# assignment_NOVA_TEAM_light_control_syste.net
KiCad netlist of a schematic drawn in EasyEDA
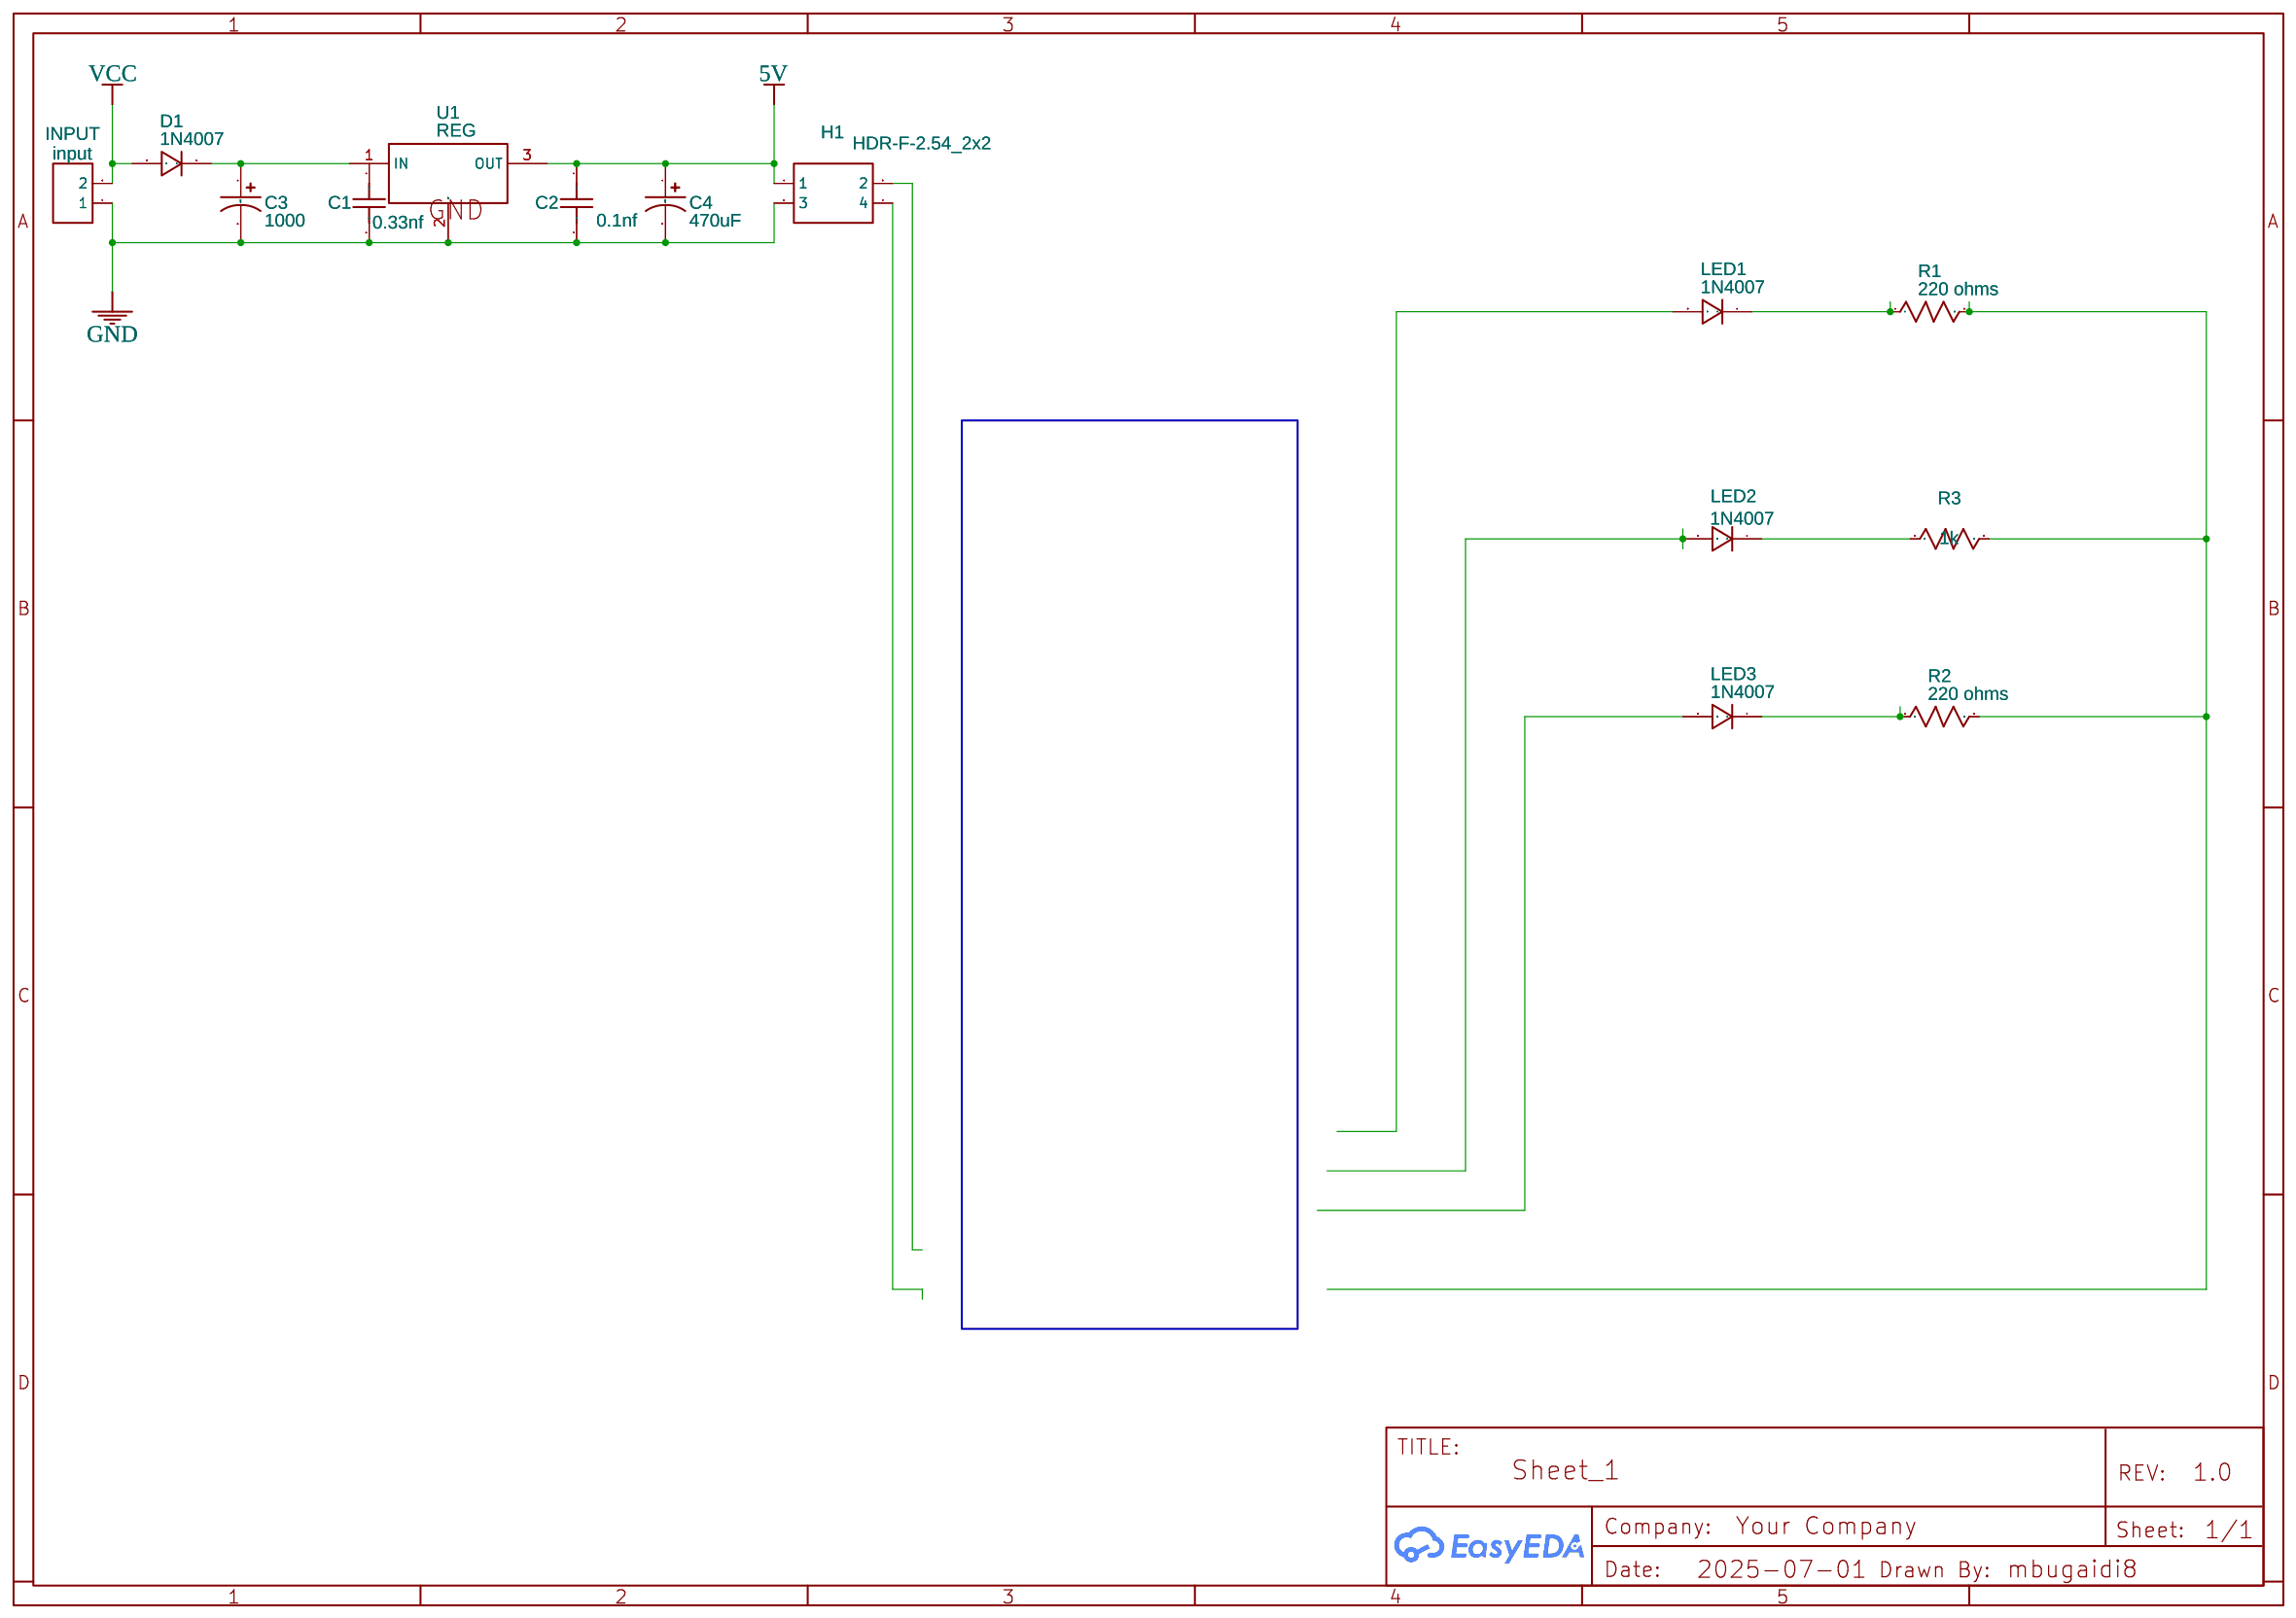
[diagram p0: schematic sheet]

(export (version "E")
  (design (tool "Eeschema 10.0.6"))
  (components
    (comp (ref "C1") (value "0.33nf") (libsource (lib "") (part "C_RAD-0.1_US")))
    (comp (ref "C2") (value "0.1nf") (libsource (lib "") (part "C_RAD-0.1_US")))
    (comp (ref "C3") (value "1000") (libsource (lib "") (part "CE_TH_D3.0×F1.5_US_1")))
    (comp (ref "C4") (value "470uF") (libsource (lib "") (part "CE_TH_D3.0×F1.5_US")))
    (comp (ref "D1")
      (value "1N4007")
      (fields (field (name "Manufacturer") "SEMTECH"))
      (libsource (lib "") (part "1N4007_1"))
    )
    (comp (ref "H1") (value "HDR-F-2.54_2x2") (libsource (lib "") (part "HDR-F-2.54_2x2")))
    (comp (ref "INPUT") (value "input") (libsource (lib "") (part "CONN-TH_2P-P5.00")))
    (comp (ref "LED1")
      (value "1N4007")
      (fields (field (name "Manufacturer") "SEMTECH"))
      (libsource (lib "") (part "1N4007"))
    )
    (comp (ref "LED2")
      (value "1N4007")
      (fields (field (name "Manufacturer") "SEMTECH"))
      (libsource (lib "") (part "1N4007"))
    )
    (comp (ref "LED3")
      (value "1N4007")
      (fields (field (name "Manufacturer") "SEMTECH"))
      (libsource (lib "") (part "1N4007"))
    )
    (comp (ref "R1") (value "220 ohms") (libsource (lib "") (part "R_0603_US")))
    (comp (ref "R2") (value "220 ohms") (libsource (lib "") (part "R_0603_US")))
    (comp (ref "R3") (value "1k") (libsource (lib "") (part "R_0603_US")))
    (comp (ref "U1")
      (value "REG")
      (fields
        (field (name "Manufacturer Part") "L7805CV-DG")
        (field (name "Manufacturer") "STMicroelectronics")
      )
      (libsource (lib "") (part "7805(TO-220)"))
    )
  )
  (nets
    (net (code "1") (name "5V") (class "Default")
      (node (ref "C2") (pin "1") (pinfunction "1_1") (pintype "unspecified"))
      (node (ref "C4") (pin "1") (pinfunction "1_1") (pintype "unspecified"))
      (node (ref "H1") (pin "1") (pinfunction "1_1") (pintype "unspecified"))
      (node (ref "U1") (pin "3") (pinfunction "OUT_3") (pintype "passive"))
    )
    (net (code "2") (name "GND") (class "Default")
      (node (ref "C1") (pin "2") (pinfunction "2_2") (pintype "unspecified"))
      (node (ref "C2") (pin "2") (pinfunction "2_2") (pintype "unspecified"))
      (node (ref "C3") (pin "2") (pinfunction "2_2") (pintype "unspecified"))
      (node (ref "C4") (pin "2") (pinfunction "2_2") (pintype "unspecified"))
      (node (ref "H1") (pin "3") (pinfunction "3_3") (pintype "unspecified"))
      (node (ref "INPUT") (pin "1") (pinfunction "1_1") (pintype "unspecified"))
      (node (ref "U1") (pin "2") (pinfunction "GND_2") (pintype "passive"))
    )
    (net (code "3") (name "Net-(LED1-Pad1)") (class "Default")
      (node (ref "LED1") (pin "1") (pinfunction "1_1") (pintype "unspecified"))
      (node (ref "R1") (pin "1") (pinfunction "1_1") (pintype "unspecified"))
    )
    (net (code "4") (name "Net-(LED2-Pad1)") (class "Default")
      (node (ref "LED2") (pin "1") (pinfunction "1_1") (pintype "unspecified"))
      (node (ref "R3") (pin "1") (pinfunction "1_1") (pintype "unspecified"))
    )
    (net (code "5") (name "Net-(LED3-Pad1)") (class "Default")
      (node (ref "LED3") (pin "1") (pinfunction "1_1") (pintype "unspecified"))
      (node (ref "R2") (pin "1") (pinfunction "1_1") (pintype "unspecified"))
    )
    (net (code "6") (name "Net-(R1-Pad2)") (class "Default")
      (node (ref "R1") (pin "2") (pinfunction "2_2") (pintype "unspecified"))
      (node (ref "R2") (pin "2") (pinfunction "2_2") (pintype "unspecified"))
      (node (ref "R3") (pin "2") (pinfunction "2_2") (pintype "unspecified"))
    )
    (net (code "7") (name "Net-(U1-IN)") (class "Default")
      (node (ref "C3") (pin "1") (pinfunction "1_1") (pintype "unspecified"))
      (node (ref "D1") (pin "1") (pinfunction "1_1") (pintype "unspecified"))
      (node (ref "U1") (pin "1") (pinfunction "IN_1") (pintype "passive"))
    )
    (net (code "8") (name "VCC") (class "Default")
      (node (ref "D1") (pin "2") (pinfunction "2_2") (pintype "unspecified"))
      (node (ref "INPUT") (pin "2") (pinfunction "2_2") (pintype "unspecified"))
    )
    (net (code "9") (name "unconnected-(C1-Pad1)") (class "Default")
      (node (ref "C1") (pin "1") (pinfunction "1_1") (pintype "unspecified"))
    )
    (net (code "10") (name "unconnected-(H1-Pad2)") (class "Default")
      (node (ref "H1") (pin "2") (pinfunction "2_2") (pintype "unspecified"))
    )
    (net (code "11") (name "unconnected-(H1-Pad4)") (class "Default")
      (node (ref "H1") (pin "4") (pinfunction "4_4") (pintype "unspecified"))
    )
    (net (code "12") (name "unconnected-(LED1-Pad2)") (class "Default")
      (node (ref "LED1") (pin "2") (pinfunction "2_2") (pintype "unspecified"))
    )
    (net (code "13") (name "unconnected-(LED2-Pad2)") (class "Default")
      (node (ref "LED2") (pin "2") (pinfunction "2_2") (pintype "unspecified"))
    )
    (net (code "14") (name "unconnected-(LED3-Pad2)") (class "Default")
      (node (ref "LED3") (pin "2") (pinfunction "2_2") (pintype "unspecified"))
    )
  )
)
